# turni.net
KiCad netlist of a schematic drawn in EAGLE
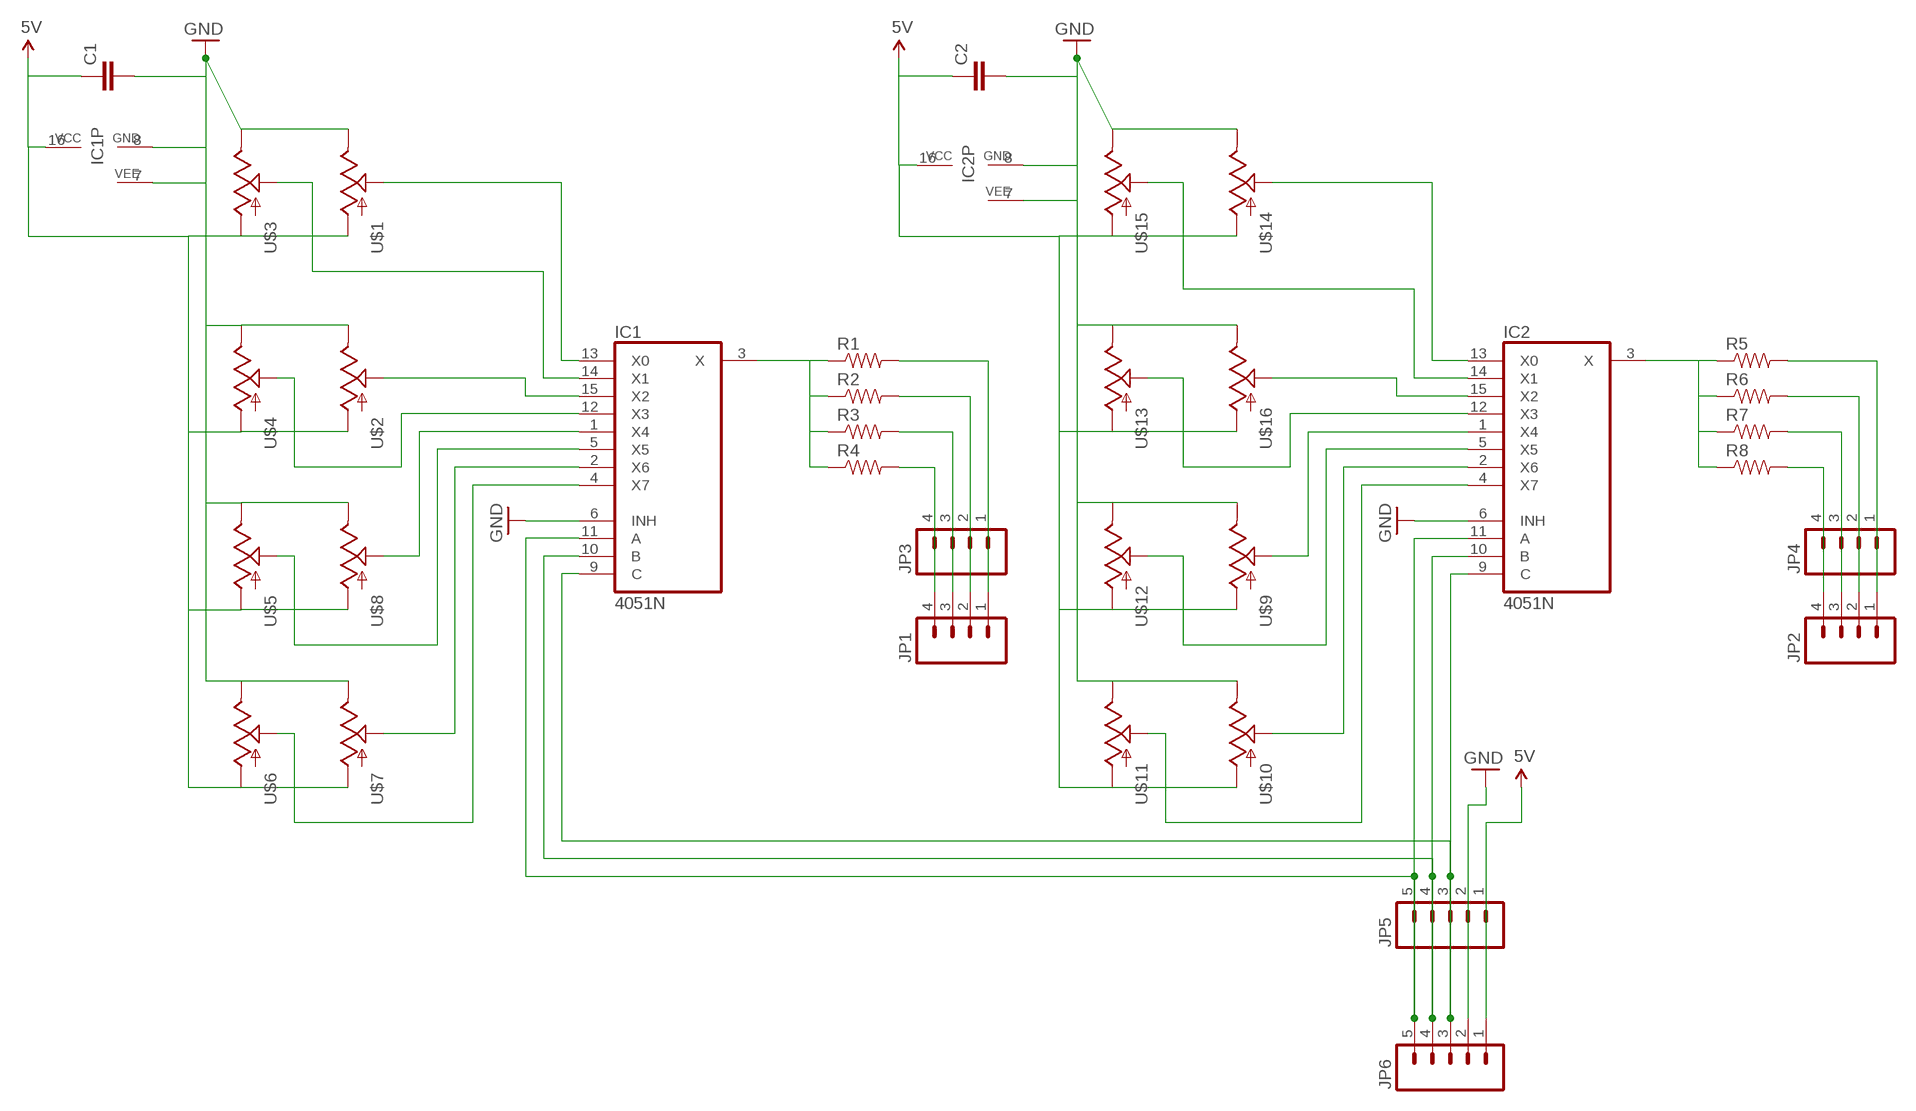
[diagram p0: schematic, sheet 1]

(export (version "E")
  (design (tool "Eeschema 10.0.6"))
  (components
    (comp (ref "C1")
      (value "CAPPTH")
      (footprint "eagle-import:CAP-PTH-SMALL")
      (libsource (lib "eagle-import") (part "CAPPTH"))
    )
    (comp (ref "C2")
      (value "CAPPTH")
      (footprint "eagle-import:CAP-PTH-SMALL")
      (libsource (lib "eagle-import") (part "CAPPTH"))
    )
    (comp (ref "IC1")
      (value "4051N")
      (footprint "eagle-import:DIL16")
      (libsource (lib "eagle-import") (part "4051N"))
    )
    (comp (ref "IC2")
      (value "4051N")
      (footprint "eagle-import:DIL16")
      (libsource (lib "eagle-import") (part "4051N"))
    )
    (comp (ref "JP1")
      (value "M04PTH")
      (footprint "eagle-import:1X04")
      (libsource (lib "eagle-import") (part "M04PTH"))
    )
    (comp (ref "JP2")
      (value "M04PTH")
      (footprint "eagle-import:1X04")
      (libsource (lib "eagle-import") (part "M04PTH"))
    )
    (comp (ref "JP3")
      (value "M04PTH")
      (footprint "eagle-import:1X04")
      (libsource (lib "eagle-import") (part "M04PTH"))
    )
    (comp (ref "JP4")
      (value "M04PTH")
      (footprint "eagle-import:1X04")
      (libsource (lib "eagle-import") (part "M04PTH"))
    )
    (comp (ref "JP5")
      (value "M05PTH")
      (footprint "eagle-import:1X05")
      (libsource (lib "eagle-import") (part "M05PTH"))
    )
    (comp (ref "JP6")
      (value "M05PTH")
      (footprint "eagle-import:1X05")
      (libsource (lib "eagle-import") (part "M05PTH"))
    )
    (comp (ref "R1")
      (value "RESISTORAXIAL-0.3")
      (footprint "eagle-import:AXIAL-0.3")
      (libsource (lib "eagle-import") (part "RESISTORAXIAL-0.3"))
    )
    (comp (ref "R2")
      (value "RESISTORAXIAL-0.3")
      (footprint "eagle-import:AXIAL-0.3")
      (libsource (lib "eagle-import") (part "RESISTORAXIAL-0.3"))
    )
    (comp (ref "R3")
      (value "RESISTORAXIAL-0.3")
      (footprint "eagle-import:AXIAL-0.3")
      (libsource (lib "eagle-import") (part "RESISTORAXIAL-0.3"))
    )
    (comp (ref "R4")
      (value "RESISTORAXIAL-0.3")
      (footprint "eagle-import:AXIAL-0.3")
      (libsource (lib "eagle-import") (part "RESISTORAXIAL-0.3"))
    )
    (comp (ref "R5")
      (value "RESISTORAXIAL-0.3")
      (footprint "eagle-import:AXIAL-0.3")
      (libsource (lib "eagle-import") (part "RESISTORAXIAL-0.3"))
    )
    (comp (ref "R6")
      (value "RESISTORAXIAL-0.3")
      (footprint "eagle-import:AXIAL-0.3")
      (libsource (lib "eagle-import") (part "RESISTORAXIAL-0.3"))
    )
    (comp (ref "R7")
      (value "RESISTORAXIAL-0.3")
      (footprint "eagle-import:AXIAL-0.3")
      (libsource (lib "eagle-import") (part "RESISTORAXIAL-0.3"))
    )
    (comp (ref "R8")
      (value "RESISTORAXIAL-0.3")
      (footprint "eagle-import:AXIAL-0.3")
      (libsource (lib "eagle-import") (part "RESISTORAXIAL-0.3"))
    )
    (comp (ref "U$1")
      (value "POT")
      (footprint "eagle-import:ALPS_POT")
      (libsource (lib "eagle-import") (part "POT"))
    )
    (comp (ref "U$2")
      (value "POT")
      (footprint "eagle-import:ALPS_POT")
      (libsource (lib "eagle-import") (part "POT"))
    )
    (comp (ref "U$3")
      (value "POT")
      (footprint "eagle-import:ALPS_POT")
      (libsource (lib "eagle-import") (part "POT"))
    )
    (comp (ref "U$4")
      (value "POT")
      (footprint "eagle-import:ALPS_POT")
      (libsource (lib "eagle-import") (part "POT"))
    )
    (comp (ref "U$5")
      (value "POT")
      (footprint "eagle-import:ALPS_POT")
      (libsource (lib "eagle-import") (part "POT"))
    )
    (comp (ref "U$6")
      (value "POT")
      (footprint "eagle-import:ALPS_POT")
      (libsource (lib "eagle-import") (part "POT"))
    )
    (comp (ref "U$7")
      (value "POT")
      (footprint "eagle-import:ALPS_POT")
      (libsource (lib "eagle-import") (part "POT"))
    )
    (comp (ref "U$8")
      (value "POT")
      (footprint "eagle-import:ALPS_POT")
      (libsource (lib "eagle-import") (part "POT"))
    )
    (comp (ref "U$9")
      (value "POT")
      (footprint "eagle-import:ALPS_POT")
      (libsource (lib "eagle-import") (part "POT"))
    )
    (comp (ref "U$10")
      (value "POT")
      (footprint "eagle-import:ALPS_POT")
      (libsource (lib "eagle-import") (part "POT"))
    )
    (comp (ref "U$11")
      (value "POT")
      (footprint "eagle-import:ALPS_POT")
      (libsource (lib "eagle-import") (part "POT"))
    )
    (comp (ref "U$12")
      (value "POT")
      (footprint "eagle-import:ALPS_POT")
      (libsource (lib "eagle-import") (part "POT"))
    )
    (comp (ref "U$13")
      (value "POT")
      (footprint "eagle-import:ALPS_POT")
      (libsource (lib "eagle-import") (part "POT"))
    )
    (comp (ref "U$14")
      (value "POT")
      (footprint "eagle-import:ALPS_POT")
      (libsource (lib "eagle-import") (part "POT"))
    )
    (comp (ref "U$15")
      (value "POT")
      (footprint "eagle-import:ALPS_POT")
      (libsource (lib "eagle-import") (part "POT"))
    )
    (comp (ref "U$16")
      (value "POT")
      (footprint "eagle-import:ALPS_POT")
      (libsource (lib "eagle-import") (part "POT"))
    )
  )
  (nets
    (net (code "1") (name "5V") (class "Default")
      (node (ref "C1") (pin "1") (pinfunction "1_1") (pintype "passive"))
      (node (ref "C2") (pin "1") (pinfunction "1_1") (pintype "passive"))
      (node (ref "IC1") (pin "16") (pinfunction "VCC_16") (pintype "power_in"))
      (node (ref "IC2") (pin "16") (pinfunction "VCC_16") (pintype "power_in"))
      (node (ref "JP5") (pin "1") (pinfunction "1_1") (pintype "passive"))
      (node (ref "JP6") (pin "1") (pinfunction "1_1") (pintype "passive"))
      (node (ref "U$1") (pin "P$3") (pinfunction "A_P$3") (pintype "passive"))
      (node (ref "U$10") (pin "P$3") (pinfunction "A_P$3") (pintype "passive"))
      (node (ref "U$11") (pin "P$3") (pinfunction "A_P$3") (pintype "passive"))
      (node (ref "U$12") (pin "P$3") (pinfunction "A_P$3") (pintype "passive"))
      (node (ref "U$13") (pin "P$3") (pinfunction "A_P$3") (pintype "passive"))
      (node (ref "U$14") (pin "P$3") (pinfunction "A_P$3") (pintype "passive"))
      (node (ref "U$15") (pin "P$3") (pinfunction "A_P$3") (pintype "passive"))
      (node (ref "U$16") (pin "P$3") (pinfunction "A_P$3") (pintype "passive"))
      (node (ref "U$2") (pin "P$3") (pinfunction "A_P$3") (pintype "passive"))
      (node (ref "U$3") (pin "P$3") (pinfunction "A_P$3") (pintype "passive"))
      (node (ref "U$4") (pin "P$3") (pinfunction "A_P$3") (pintype "passive"))
      (node (ref "U$5") (pin "P$3") (pinfunction "A_P$3") (pintype "passive"))
      (node (ref "U$6") (pin "P$3") (pinfunction "A_P$3") (pintype "passive"))
      (node (ref "U$7") (pin "P$3") (pinfunction "A_P$3") (pintype "passive"))
      (node (ref "U$8") (pin "P$3") (pinfunction "A_P$3") (pintype "passive"))
      (node (ref "U$9") (pin "P$3") (pinfunction "A_P$3") (pintype "passive"))
    )
    (net (code "2") (name "GND") (class "Default")
      (node (ref "C1") (pin "2") (pinfunction "2_2") (pintype "passive"))
      (node (ref "C2") (pin "2") (pinfunction "2_2") (pintype "passive"))
      (node (ref "IC1") (pin "6") (pinfunction "INH_6") (pintype "input"))
      (node (ref "IC1") (pin "7") (pinfunction "VEE_7") (pintype "power_in"))
      (node (ref "IC1") (pin "8") (pinfunction "GND_8") (pintype "power_in"))
      (node (ref "IC2") (pin "6") (pinfunction "INH_6") (pintype "input"))
      (node (ref "IC2") (pin "7") (pinfunction "VEE_7") (pintype "power_in"))
      (node (ref "IC2") (pin "8") (pinfunction "GND_8") (pintype "power_in"))
      (node (ref "JP5") (pin "2") (pinfunction "2_2") (pintype "passive"))
      (node (ref "JP6") (pin "2") (pinfunction "2_2") (pintype "passive"))
      (node (ref "U$1") (pin "P$1") (pinfunction "E_P$1") (pintype "passive"))
      (node (ref "U$10") (pin "P$1") (pinfunction "E_P$1") (pintype "passive"))
      (node (ref "U$11") (pin "P$1") (pinfunction "E_P$1") (pintype "passive"))
      (node (ref "U$12") (pin "P$1") (pinfunction "E_P$1") (pintype "passive"))
      (node (ref "U$13") (pin "P$1") (pinfunction "E_P$1") (pintype "passive"))
      (node (ref "U$14") (pin "P$1") (pinfunction "E_P$1") (pintype "passive"))
      (node (ref "U$15") (pin "P$1") (pinfunction "E_P$1") (pintype "passive"))
      (node (ref "U$16") (pin "P$1") (pinfunction "E_P$1") (pintype "passive"))
      (node (ref "U$2") (pin "P$1") (pinfunction "E_P$1") (pintype "passive"))
      (node (ref "U$3") (pin "P$1") (pinfunction "E_P$1") (pintype "passive"))
      (node (ref "U$4") (pin "P$1") (pinfunction "E_P$1") (pintype "passive"))
      (node (ref "U$5") (pin "P$1") (pinfunction "E_P$1") (pintype "passive"))
      (node (ref "U$6") (pin "P$1") (pinfunction "E_P$1") (pintype "passive"))
      (node (ref "U$7") (pin "P$1") (pinfunction "E_P$1") (pintype "passive"))
      (node (ref "U$8") (pin "P$1") (pinfunction "E_P$1") (pintype "passive"))
      (node (ref "U$9") (pin "P$1") (pinfunction "E_P$1") (pintype "passive"))
    )
    (net (code "3") (name "Net-(IC1A-A)") (class "Default")
      (node (ref "IC1") (pin "11") (pinfunction "A_11") (pintype "input"))
      (node (ref "IC2") (pin "11") (pinfunction "A_11") (pintype "input"))
      (node (ref "JP5") (pin "5") (pinfunction "5_5") (pintype "passive"))
      (node (ref "JP6") (pin "5") (pinfunction "5_5") (pintype "passive"))
    )
    (net (code "4") (name "Net-(IC1A-B)") (class "Default")
      (node (ref "IC1") (pin "10") (pinfunction "B_10") (pintype "input"))
      (node (ref "IC2") (pin "10") (pinfunction "B_10") (pintype "input"))
      (node (ref "JP5") (pin "4") (pinfunction "4_4") (pintype "passive"))
      (node (ref "JP6") (pin "4") (pinfunction "4_4") (pintype "passive"))
    )
    (net (code "5") (name "Net-(IC1A-C)") (class "Default")
      (node (ref "IC1") (pin "9") (pinfunction "C_9") (pintype "input"))
      (node (ref "IC2") (pin "9") (pinfunction "C_9") (pintype "input"))
      (node (ref "JP5") (pin "3") (pinfunction "3_3") (pintype "passive"))
      (node (ref "JP6") (pin "3") (pinfunction "3_3") (pintype "passive"))
    )
    (net (code "6") (name "Net-(IC1A-X)") (class "Default")
      (node (ref "IC1") (pin "3") (pinfunction "X_3") (pintype "bidirectional"))
      (node (ref "R1") (pin "P$1") (pinfunction "1_P$1") (pintype "passive"))
      (node (ref "R2") (pin "P$1") (pinfunction "1_P$1") (pintype "passive"))
      (node (ref "R3") (pin "P$1") (pinfunction "1_P$1") (pintype "passive"))
      (node (ref "R4") (pin "P$1") (pinfunction "1_P$1") (pintype "passive"))
    )
    (net (code "7") (name "Net-(IC1A-X0)") (class "Default")
      (node (ref "IC1") (pin "13") (pinfunction "X0_13") (pintype "bidirectional"))
      (node (ref "U$1") (pin "P$2") (pinfunction "S_P$2") (pintype "passive"))
    )
    (net (code "8") (name "Net-(IC1A-X1)") (class "Default")
      (node (ref "IC1") (pin "14") (pinfunction "X1_14") (pintype "bidirectional"))
      (node (ref "U$3") (pin "P$2") (pinfunction "S_P$2") (pintype "passive"))
    )
    (net (code "9") (name "Net-(IC1A-X2)") (class "Default")
      (node (ref "IC1") (pin "15") (pinfunction "X2_15") (pintype "bidirectional"))
      (node (ref "U$2") (pin "P$2") (pinfunction "S_P$2") (pintype "passive"))
    )
    (net (code "10") (name "Net-(IC1A-X3)") (class "Default")
      (node (ref "IC1") (pin "12") (pinfunction "X3_12") (pintype "bidirectional"))
      (node (ref "U$4") (pin "P$2") (pinfunction "S_P$2") (pintype "passive"))
    )
    (net (code "11") (name "Net-(IC1A-X4)") (class "Default")
      (node (ref "IC1") (pin "1") (pinfunction "X4_1") (pintype "bidirectional"))
      (node (ref "U$8") (pin "P$2") (pinfunction "S_P$2") (pintype "passive"))
    )
    (net (code "12") (name "Net-(IC1A-X5)") (class "Default")
      (node (ref "IC1") (pin "5") (pinfunction "X5_5") (pintype "bidirectional"))
      (node (ref "U$5") (pin "P$2") (pinfunction "S_P$2") (pintype "passive"))
    )
    (net (code "13") (name "Net-(IC1A-X6)") (class "Default")
      (node (ref "IC1") (pin "2") (pinfunction "X6_2") (pintype "bidirectional"))
      (node (ref "U$7") (pin "P$2") (pinfunction "S_P$2") (pintype "passive"))
    )
    (net (code "14") (name "Net-(IC1A-X7)") (class "Default")
      (node (ref "IC1") (pin "4") (pinfunction "X7_4") (pintype "bidirectional"))
      (node (ref "U$6") (pin "P$2") (pinfunction "S_P$2") (pintype "passive"))
    )
    (net (code "15") (name "Net-(IC2A-X)") (class "Default")
      (node (ref "IC2") (pin "3") (pinfunction "X_3") (pintype "bidirectional"))
      (node (ref "R5") (pin "P$1") (pinfunction "1_P$1") (pintype "passive"))
      (node (ref "R6") (pin "P$1") (pinfunction "1_P$1") (pintype "passive"))
      (node (ref "R7") (pin "P$1") (pinfunction "1_P$1") (pintype "passive"))
      (node (ref "R8") (pin "P$1") (pinfunction "1_P$1") (pintype "passive"))
    )
    (net (code "16") (name "Net-(IC2A-X0)") (class "Default")
      (node (ref "IC2") (pin "13") (pinfunction "X0_13") (pintype "bidirectional"))
      (node (ref "U$14") (pin "P$2") (pinfunction "S_P$2") (pintype "passive"))
    )
    (net (code "17") (name "Net-(IC2A-X1)") (class "Default")
      (node (ref "IC2") (pin "14") (pinfunction "X1_14") (pintype "bidirectional"))
      (node (ref "U$15") (pin "P$2") (pinfunction "S_P$2") (pintype "passive"))
    )
    (net (code "18") (name "Net-(IC2A-X2)") (class "Default")
      (node (ref "IC2") (pin "15") (pinfunction "X2_15") (pintype "bidirectional"))
      (node (ref "U$16") (pin "P$2") (pinfunction "S_P$2") (pintype "passive"))
    )
    (net (code "19") (name "Net-(IC2A-X3)") (class "Default")
      (node (ref "IC2") (pin "12") (pinfunction "X3_12") (pintype "bidirectional"))
      (node (ref "U$13") (pin "P$2") (pinfunction "S_P$2") (pintype "passive"))
    )
    (net (code "20") (name "Net-(IC2A-X4)") (class "Default")
      (node (ref "IC2") (pin "1") (pinfunction "X4_1") (pintype "bidirectional"))
      (node (ref "U$9") (pin "P$2") (pinfunction "S_P$2") (pintype "passive"))
    )
    (net (code "21") (name "Net-(IC2A-X5)") (class "Default")
      (node (ref "IC2") (pin "5") (pinfunction "X5_5") (pintype "bidirectional"))
      (node (ref "U$12") (pin "P$2") (pinfunction "S_P$2") (pintype "passive"))
    )
    (net (code "22") (name "Net-(IC2A-X6)") (class "Default")
      (node (ref "IC2") (pin "2") (pinfunction "X6_2") (pintype "bidirectional"))
      (node (ref "U$10") (pin "P$2") (pinfunction "S_P$2") (pintype "passive"))
    )
    (net (code "23") (name "Net-(IC2A-X7)") (class "Default")
      (node (ref "IC2") (pin "4") (pinfunction "X7_4") (pintype "bidirectional"))
      (node (ref "U$11") (pin "P$2") (pinfunction "S_P$2") (pintype "passive"))
    )
    (net (code "24") (name "Net-(R1-2)") (class "Default")
      (node (ref "JP1") (pin "1") (pinfunction "1_1") (pintype "passive"))
      (node (ref "JP3") (pin "1") (pinfunction "1_1") (pintype "passive"))
      (node (ref "R1") (pin "P$2") (pinfunction "2_P$2") (pintype "passive"))
    )
    (net (code "25") (name "Net-(R2-2)") (class "Default")
      (node (ref "JP1") (pin "2") (pinfunction "2_2") (pintype "passive"))
      (node (ref "JP3") (pin "2") (pinfunction "2_2") (pintype "passive"))
      (node (ref "R2") (pin "P$2") (pinfunction "2_P$2") (pintype "passive"))
    )
    (net (code "26") (name "Net-(R3-2)") (class "Default")
      (node (ref "JP1") (pin "3") (pinfunction "3_3") (pintype "passive"))
      (node (ref "JP3") (pin "3") (pinfunction "3_3") (pintype "passive"))
      (node (ref "R3") (pin "P$2") (pinfunction "2_P$2") (pintype "passive"))
    )
    (net (code "27") (name "Net-(R4-2)") (class "Default")
      (node (ref "JP1") (pin "4") (pinfunction "4_4") (pintype "passive"))
      (node (ref "JP3") (pin "4") (pinfunction "4_4") (pintype "passive"))
      (node (ref "R4") (pin "P$2") (pinfunction "2_P$2") (pintype "passive"))
    )
    (net (code "28") (name "Net-(R5-2)") (class "Default")
      (node (ref "JP2") (pin "1") (pinfunction "1_1") (pintype "passive"))
      (node (ref "JP4") (pin "1") (pinfunction "1_1") (pintype "passive"))
      (node (ref "R5") (pin "P$2") (pinfunction "2_P$2") (pintype "passive"))
    )
    (net (code "29") (name "Net-(R6-2)") (class "Default")
      (node (ref "JP2") (pin "2") (pinfunction "2_2") (pintype "passive"))
      (node (ref "JP4") (pin "2") (pinfunction "2_2") (pintype "passive"))
      (node (ref "R6") (pin "P$2") (pinfunction "2_P$2") (pintype "passive"))
    )
    (net (code "30") (name "Net-(R7-2)") (class "Default")
      (node (ref "JP2") (pin "3") (pinfunction "3_3") (pintype "passive"))
      (node (ref "JP4") (pin "3") (pinfunction "3_3") (pintype "passive"))
      (node (ref "R7") (pin "P$2") (pinfunction "2_P$2") (pintype "passive"))
    )
    (net (code "31") (name "Net-(R8-2)") (class "Default")
      (node (ref "JP2") (pin "4") (pinfunction "4_4") (pintype "passive"))
      (node (ref "JP4") (pin "4") (pinfunction "4_4") (pintype "passive"))
      (node (ref "R8") (pin "P$2") (pinfunction "2_P$2") (pintype "passive"))
    )
  )
)
